# EXI.net
KiCad netlist of a schematic drawn in EasyEDA
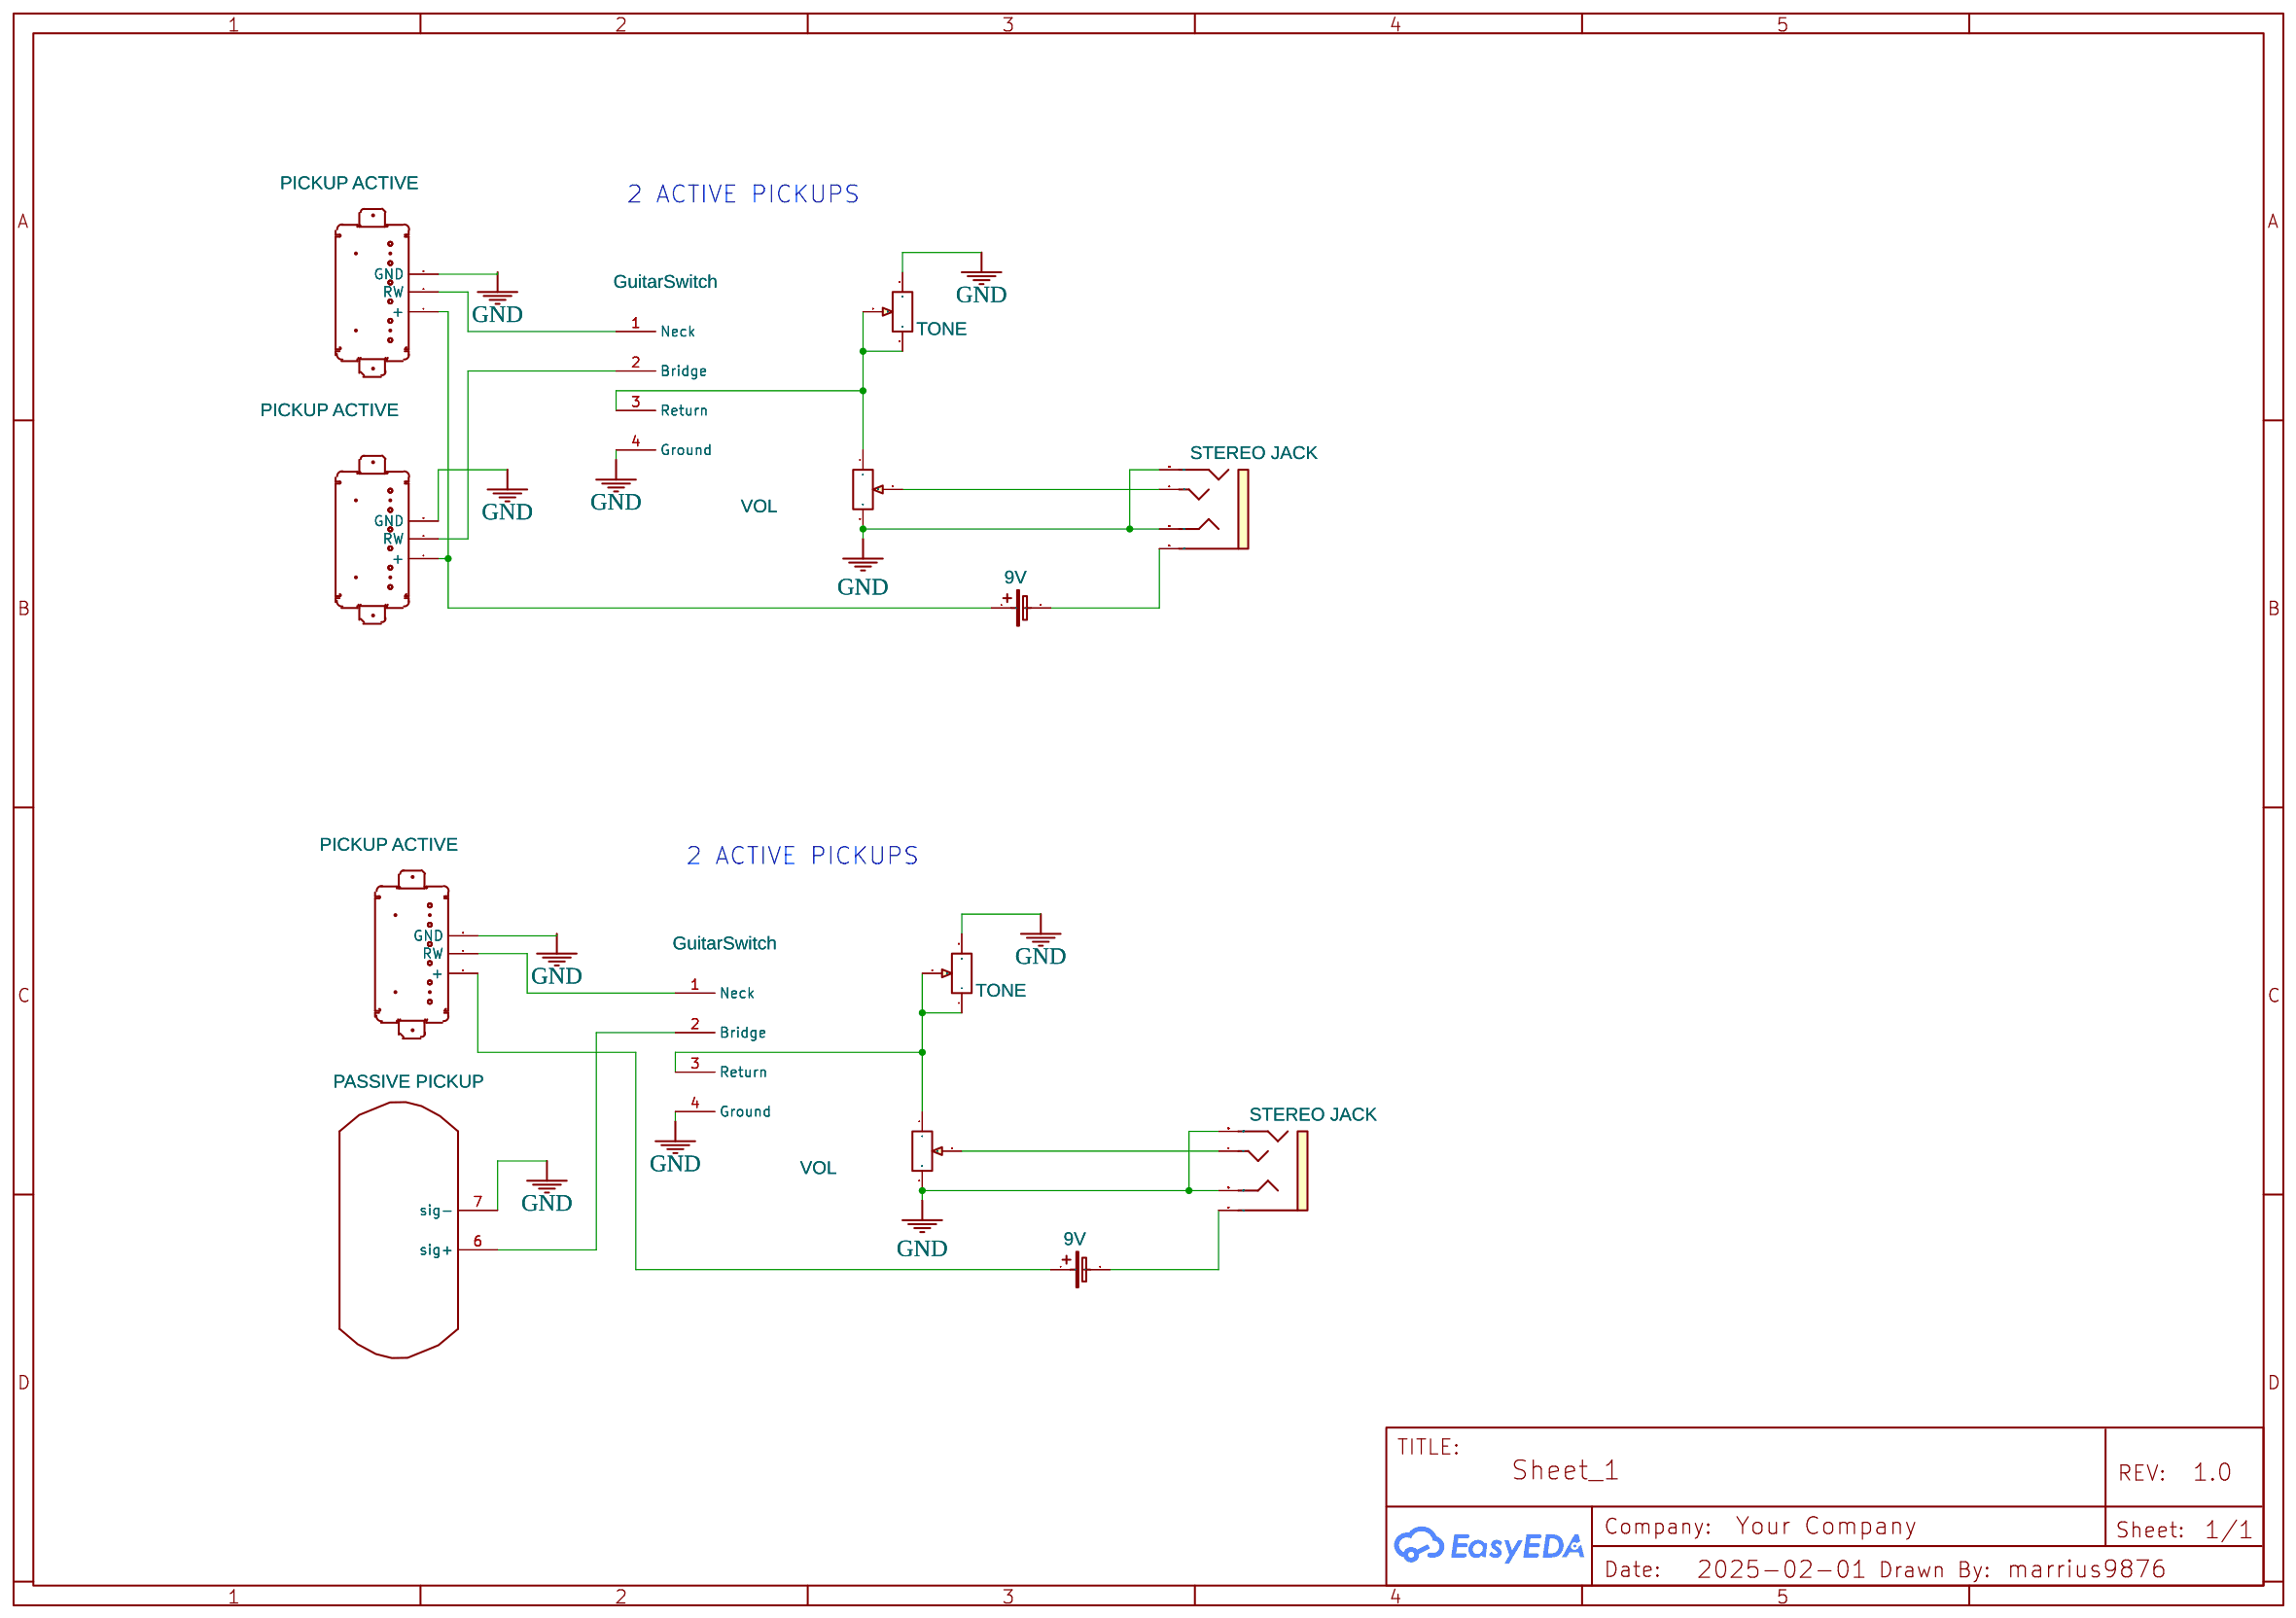
[diagram p0: schematic sheet]

(export (version "E")
  (design (tool "Eeschema 10.0.6"))
  (components
    (comp (ref "BT1") (value "9V") (libsource (lib "") (part "Device_Battery_Cell")))
    (comp (ref "BT2") (value "9V") (libsource (lib "") (part "Device_Battery_Cell")))
    (comp (ref "RP1") (value "VOL") (libsource (lib "") (part "R_3386P_EU_1")))
    (comp (ref "RP2") (value "TONE") (libsource (lib "") (part "R_3386P_EU")))
    (comp (ref "RP3") (value "TONE") (libsource (lib "") (part "R_3386P_EU")))
    (comp (ref "RP4") (value "VOL") (libsource (lib "") (part "R_3386P_EU_1")))
    (comp (ref "SW1") (value "GuitarSwitch") (libsource (lib "") (part "GuitarSwitch")))
    (comp (ref "SW2") (value "GuitarSwitch") (libsource (lib "") (part "GuitarSwitch")))
    (comp (ref "U1") (value "PICKUP ACTIVE") (libsource (lib "") (part "Humbucker")))
    (comp (ref "U2") (value "PICKUP ACTIVE") (libsource (lib "") (part "Humbucker")))
    (comp (ref "U3") (value "STEREO JACK") (libsource (lib "") (part "AUDIO-JACK3")))
    (comp (ref "U4") (value "STEREO JACK") (libsource (lib "") (part "AUDIO-JACK3")))
    (comp (ref "U5") (value "PICKUP ACTIVE") (libsource (lib "") (part "Humbucker")))
    (comp (ref "U6") (value "PASSIVE PICKUP") (libsource (lib "") (part "single_coil")))
  )
  (nets
    (net (code "1") (name "GND") (class "Default")
      (node (ref "RP1") (pin "3") (pinfunction "3_3") (pintype "input"))
      (node (ref "RP2") (pin "3") (pinfunction "3_3") (pintype "input"))
      (node (ref "RP3") (pin "3") (pinfunction "3_3") (pintype "input"))
      (node (ref "RP4") (pin "3") (pinfunction "3_3") (pintype "input"))
      (node (ref "SW1") (pin "4") (pinfunction "Ground_4") (pintype "unspecified"))
      (node (ref "SW2") (pin "4") (pinfunction "Ground_4") (pintype "unspecified"))
      (node (ref "U1") (pin "3") (pinfunction "GND_3") (pintype "unspecified"))
      (node (ref "U2") (pin "3") (pinfunction "GND_3") (pintype "unspecified"))
      (node (ref "U3") (pin "RING1") (pinfunction "RING1_RING1") (pintype "unspecified"))
      (node (ref "U3") (pin "RING2") (pinfunction "RING2_RING2") (pintype "unspecified"))
      (node (ref "U4") (pin "RING1") (pinfunction "RING1_RING1") (pintype "unspecified"))
      (node (ref "U4") (pin "RING2") (pinfunction "RING2_RING2") (pintype "unspecified"))
      (node (ref "U5") (pin "3") (pinfunction "GND_3") (pintype "unspecified"))
      (node (ref "U6") (pin "7") (pinfunction "sig-_7") (pintype "unspecified"))
    )
    (net (code "2") (name "Net-(BT1-+)") (class "Default")
      (node (ref "BT1") (pin "1") (pinfunction "+_1") (pintype "unspecified"))
      (node (ref "U1") (pin "1") (pinfunction "+_1") (pintype "unspecified"))
      (node (ref "U2") (pin "1") (pinfunction "+_1") (pintype "unspecified"))
    )
    (net (code "3") (name "Net-(BT1--)") (class "Default")
      (node (ref "BT1") (pin "2") (pinfunction "-_2") (pintype "unspecified"))
      (node (ref "U3") (pin "EARTH") (pinfunction "EARTH_EARTH") (pintype "unspecified"))
    )
    (net (code "4") (name "Net-(BT2-+)") (class "Default")
      (node (ref "BT2") (pin "1") (pinfunction "+_1") (pintype "unspecified"))
      (node (ref "U5") (pin "1") (pinfunction "+_1") (pintype "unspecified"))
    )
    (net (code "5") (name "Net-(BT2--)") (class "Default")
      (node (ref "BT2") (pin "2") (pinfunction "-_2") (pintype "unspecified"))
      (node (ref "U4") (pin "EARTH") (pinfunction "EARTH_EARTH") (pintype "unspecified"))
    )
    (net (code "6") (name "Net-(RP1-Pad2)") (class "Default")
      (node (ref "RP1") (pin "2") (pinfunction "2_2") (pintype "input"))
      (node (ref "U3") (pin "TIP") (pinfunction "TIP_TIP") (pintype "unspecified"))
    )
    (net (code "7") (name "Net-(RP4-Pad2)") (class "Default")
      (node (ref "RP4") (pin "2") (pinfunction "2_2") (pintype "input"))
      (node (ref "U4") (pin "TIP") (pinfunction "TIP_TIP") (pintype "unspecified"))
    )
    (net (code "8") (name "Net-(SW1-Bridge)") (class "Default")
      (node (ref "SW1") (pin "2") (pinfunction "Bridge_2") (pintype "unspecified"))
      (node (ref "U1") (pin "2") (pinfunction "RW_2") (pintype "unspecified"))
    )
    (net (code "9") (name "Net-(SW1-Neck)") (class "Default")
      (node (ref "SW1") (pin "1") (pinfunction "Neck_1") (pintype "unspecified"))
      (node (ref "U2") (pin "2") (pinfunction "RW_2") (pintype "unspecified"))
    )
    (net (code "10") (name "Net-(SW1-Return)") (class "Default")
      (node (ref "RP1") (pin "1") (pinfunction "1_1") (pintype "input"))
      (node (ref "RP2") (pin "1") (pinfunction "1_1") (pintype "input"))
      (node (ref "RP2") (pin "2") (pinfunction "2_2") (pintype "input"))
      (node (ref "SW1") (pin "3") (pinfunction "Return_3") (pintype "unspecified"))
    )
    (net (code "11") (name "Net-(SW2-Bridge)") (class "Default")
      (node (ref "SW2") (pin "2") (pinfunction "Bridge_2") (pintype "unspecified"))
      (node (ref "U6") (pin "6") (pinfunction "sig+_6") (pintype "unspecified"))
    )
    (net (code "12") (name "Net-(SW2-Neck)") (class "Default")
      (node (ref "SW2") (pin "1") (pinfunction "Neck_1") (pintype "unspecified"))
      (node (ref "U5") (pin "2") (pinfunction "RW_2") (pintype "unspecified"))
    )
    (net (code "13") (name "Net-(SW2-Return)") (class "Default")
      (node (ref "RP3") (pin "1") (pinfunction "1_1") (pintype "input"))
      (node (ref "RP3") (pin "2") (pinfunction "2_2") (pintype "input"))
      (node (ref "RP4") (pin "1") (pinfunction "1_1") (pintype "input"))
      (node (ref "SW2") (pin "3") (pinfunction "Return_3") (pintype "unspecified"))
    )
  )
)
